# schematic.net
KiCad netlist of a schematic drawn in EAGLE
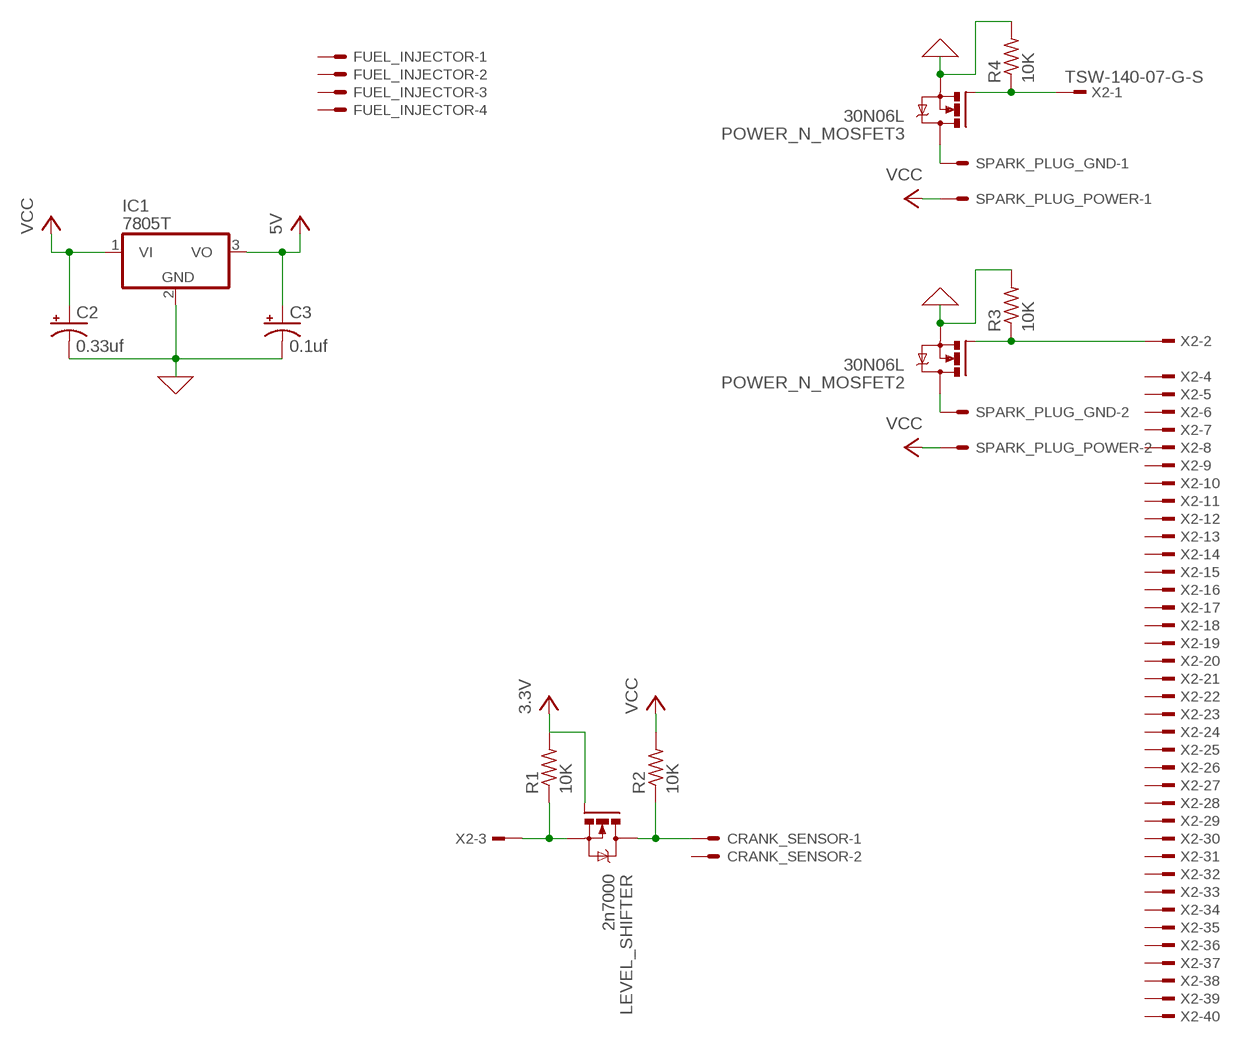
[diagram p0: schematic, sheet 1]

(export (version "E")
  (design (tool "Eeschema 10.0.6"))
  (components
    (comp (ref "C2")
      (value "0.33uf")
      (footprint "eagle-import:E2,5-5")
      (libsource (lib "eagle-import") (part "CPOL-USE2.5-5"))
    )
    (comp (ref "C3")
      (value "0.1uf")
      (footprint "eagle-import:E2,5-5")
      (libsource (lib "eagle-import") (part "CPOL-USE2.5-5"))
    )
    (comp (ref "CRANK_SENSOR")
      (value "KK-156-2")
      (footprint "eagle-import:KK-156-2")
      (fields (field (name "MF") "MOLEX"))
      (libsource (lib "eagle-import") (part "KK-156-2"))
    )
    (comp (ref "FUEL_INJECTOR")
      (value "KK-156-4")
      (footprint "eagle-import:KK-156-4")
      (fields (field (name "MF") "MOLEX"))
      (libsource (lib "eagle-import") (part "KK-156-4"))
    )
    (comp (ref "IC1")
      (value "7805T")
      (footprint "eagle-import:TO220H")
      (libsource (lib "eagle-import") (part "78T05"))
    )
    (comp (ref "LEVEL_SHIFTER")
      (value "2n7000")
      (footprint "eagle-import:TO220BV")
      (libsource (lib "eagle-import") (part "IRF520"))
    )
    (comp (ref "POWER_N_MOSFET2")
      (value "30N06L")
      (footprint "eagle-import:TO220BV")
      (libsource (lib "eagle-import") (part "IRF520"))
    )
    (comp (ref "POWER_N_MOSFET3")
      (value "30N06L")
      (footprint "eagle-import:TO220BV")
      (libsource (lib "eagle-import") (part "IRF520"))
    )
    (comp (ref "R1")
      (value "10K")
      (footprint "eagle-import:0207_7")
      (libsource (lib "eagle-import") (part "R-US_0207/7"))
    )
    (comp (ref "R2")
      (value "10K")
      (footprint "eagle-import:0207_7")
      (libsource (lib "eagle-import") (part "R-US_0207/7"))
    )
    (comp (ref "R3")
      (value "10K")
      (footprint "eagle-import:0207_7")
      (libsource (lib "eagle-import") (part "R-US_0207/7"))
    )
    (comp (ref "R4")
      (value "10K")
      (footprint "eagle-import:0207_7")
      (libsource (lib "eagle-import") (part "R-US_0207/7"))
    )
    (comp (ref "SPARK_PLUG_GND")
      (value "KK-156-2")
      (footprint "eagle-import:KK-156-2")
      (fields (field (name "MF") "MOLEX"))
      (libsource (lib "eagle-import") (part "KK-156-2"))
    )
    (comp (ref "SPARK_PLUG_POWER")
      (value "KK-156-2")
      (footprint "eagle-import:KK-156-2")
      (fields (field (name "MF") "MOLEX"))
      (libsource (lib "eagle-import") (part "KK-156-2"))
    )
    (comp (ref "X2")
      (value "TSW-140-07-G-S")
      (footprint "eagle-import:TSW-140-XX-G-S")
      (fields (field (name "MF") "Samtec Inc."))
      (libsource (lib "eagle-import") (part "TSW-140--G-S07"))
    )
  )
  (nets
    (net (code "1") (name "3.3V") (class "Default")
      (node (ref "LEVEL_SHIFTER") (pin "G") (pinfunction "G_G") (pintype "passive"))
      (node (ref "R1") (pin "2") (pinfunction "2_2") (pintype "passive"))
    )
    (net (code "2") (name "5V") (class "Default")
      (node (ref "C2") (pin "+") (pinfunction "+_+") (pintype "passive"))
      (node (ref "C3") (pin "+") (pinfunction "+_+") (pintype "passive"))
      (node (ref "IC1") (pin "1") (pinfunction "VI_1") (pintype "input"))
      (node (ref "IC1") (pin "3") (pinfunction "VO_3") (pintype "passive"))
      (node (ref "R2") (pin "2") (pinfunction "2_2") (pintype "passive"))
      (node (ref "SPARK_PLUG_POWER") (pin "1") (pinfunction "S_1") (pintype "passive"))
      (node (ref "SPARK_PLUG_POWER") (pin "2") (pinfunction "S_2") (pintype "passive"))
    )
    (net (code "3") (name "GND") (class "Default")
      (node (ref "C2") (pin "-") (pinfunction "-_-") (pintype "passive"))
      (node (ref "C3") (pin "-") (pinfunction "-_-") (pintype "passive"))
      (node (ref "IC1") (pin "2") (pinfunction "GND_2") (pintype "passive"))
      (node (ref "POWER_N_MOSFET2") (pin "S") (pinfunction "S_S") (pintype "passive"))
      (node (ref "POWER_N_MOSFET3") (pin "S") (pinfunction "S_S") (pintype "passive"))
      (node (ref "R3") (pin "2") (pinfunction "2_2") (pintype "passive"))
      (node (ref "R4") (pin "2") (pinfunction "2_2") (pintype "passive"))
    )
    (net (code "4") (name "Net-(CRANK_SENSORA-S)") (class "Default")
      (node (ref "CRANK_SENSOR") (pin "1") (pinfunction "S_1") (pintype "passive"))
      (node (ref "LEVEL_SHIFTER") (pin "D") (pinfunction "D_D") (pintype "passive"))
      (node (ref "R2") (pin "1") (pinfunction "1_1") (pintype "passive"))
    )
    (net (code "5") (name "Net-(POWER_N_MOSFET3-PadG)") (class "Default")
      (node (ref "POWER_N_MOSFET3") (pin "G") (pinfunction "G_G") (pintype "passive"))
      (node (ref "R4") (pin "1") (pinfunction "1_1") (pintype "passive"))
      (node (ref "X2") (pin "1") (pinfunction "1_1") (pintype "passive"))
    )
    (net (code "6") (name "Net-(SPARK_PLUG_GNDA-S)") (class "Default")
      (node (ref "POWER_N_MOSFET3") (pin "D") (pinfunction "D_D") (pintype "passive"))
      (node (ref "SPARK_PLUG_GND") (pin "1") (pinfunction "S_1") (pintype "passive"))
    )
    (net (code "7") (name "Net-(SPARK_PLUG_GNDB-S)") (class "Default")
      (node (ref "POWER_N_MOSFET2") (pin "D") (pinfunction "D_D") (pintype "passive"))
      (node (ref "SPARK_PLUG_GND") (pin "2") (pinfunction "S_2") (pintype "passive"))
    )
    (net (code "8") (name "Net-(X2L-1)") (class "Default")
      (node (ref "POWER_N_MOSFET2") (pin "G") (pinfunction "G_G") (pintype "passive"))
      (node (ref "R3") (pin "1") (pinfunction "1_1") (pintype "passive"))
      (node (ref "X2") (pin "2") (pinfunction "1_2") (pintype "passive"))
    )
    (net (code "9") (name "Net-(X2W-1)") (class "Default")
      (node (ref "LEVEL_SHIFTER") (pin "S") (pinfunction "S_S") (pintype "passive"))
      (node (ref "R1") (pin "1") (pinfunction "1_1") (pintype "passive"))
      (node (ref "X2") (pin "3") (pinfunction "1_3") (pintype "passive"))
    )
    (net (code "10") (name "unconnected-(CRANK_SENSORB-S-Pad2)") (class "Default")
      (node (ref "CRANK_SENSOR") (pin "2") (pinfunction "S_2") (pintype "passive"))
    )
    (net (code "11") (name "unconnected-(FUEL_INJECTORA-S-Pad1)") (class "Default")
      (node (ref "FUEL_INJECTOR") (pin "1") (pinfunction "S_1") (pintype "passive"))
    )
    (net (code "12") (name "unconnected-(FUEL_INJECTORB-S-Pad2)") (class "Default")
      (node (ref "FUEL_INJECTOR") (pin "2") (pinfunction "S_2") (pintype "passive"))
    )
    (net (code "13") (name "unconnected-(FUEL_INJECTORC-S-Pad3)") (class "Default")
      (node (ref "FUEL_INJECTOR") (pin "3") (pinfunction "S_3") (pintype "passive"))
    )
    (net (code "14") (name "unconnected-(FUEL_INJECTORD-S-Pad4)") (class "Default")
      (node (ref "FUEL_INJECTOR") (pin "4") (pinfunction "S_4") (pintype "passive"))
    )
    (net (code "15") (name "unconnected-(X2AA-1-Pad33)") (class "Default")
      (node (ref "X2") (pin "33") (pinfunction "1_33") (pintype "passive"))
    )
    (net (code "16") (name "unconnected-(X2AB-1-Pad34)") (class "Default")
      (node (ref "X2") (pin "34") (pinfunction "1_34") (pintype "passive"))
    )
    (net (code "17") (name "unconnected-(X2AC-1-Pad35)") (class "Default")
      (node (ref "X2") (pin "35") (pinfunction "1_35") (pintype "passive"))
    )
    (net (code "18") (name "unconnected-(X2AD-1-Pad36)") (class "Default")
      (node (ref "X2") (pin "36") (pinfunction "1_36") (pintype "passive"))
    )
    (net (code "19") (name "unconnected-(X2AE-1-Pad37)") (class "Default")
      (node (ref "X2") (pin "37") (pinfunction "1_37") (pintype "passive"))
    )
    (net (code "20") (name "unconnected-(X2AF-1-Pad38)") (class "Default")
      (node (ref "X2") (pin "38") (pinfunction "1_38") (pintype "passive"))
    )
    (net (code "21") (name "unconnected-(X2AG-1-Pad39)") (class "Default")
      (node (ref "X2") (pin "39") (pinfunction "1_39") (pintype "passive"))
    )
    (net (code "22") (name "unconnected-(X2AH-1-Pad4)") (class "Default")
      (node (ref "X2") (pin "4") (pinfunction "1_4") (pintype "passive"))
    )
    (net (code "23") (name "unconnected-(X2AI-1-Pad40)") (class "Default")
      (node (ref "X2") (pin "40") (pinfunction "1_40") (pintype "passive"))
    )
    (net (code "24") (name "unconnected-(X2AJ-1-Pad5)") (class "Default")
      (node (ref "X2") (pin "5") (pinfunction "1_5") (pintype "passive"))
    )
    (net (code "25") (name "unconnected-(X2AK-1-Pad6)") (class "Default")
      (node (ref "X2") (pin "6") (pinfunction "1_6") (pintype "passive"))
    )
    (net (code "26") (name "unconnected-(X2AL-1-Pad7)") (class "Default")
      (node (ref "X2") (pin "7") (pinfunction "1_7") (pintype "passive"))
    )
    (net (code "27") (name "unconnected-(X2AM-1-Pad8)") (class "Default")
      (node (ref "X2") (pin "8") (pinfunction "1_8") (pintype "passive"))
    )
    (net (code "28") (name "unconnected-(X2AN-1-Pad9)") (class "Default")
      (node (ref "X2") (pin "9") (pinfunction "1_9") (pintype "passive"))
    )
    (net (code "29") (name "unconnected-(X2B-1-Pad10)") (class "Default")
      (node (ref "X2") (pin "10") (pinfunction "1_10") (pintype "passive"))
    )
    (net (code "30") (name "unconnected-(X2C-1-Pad11)") (class "Default")
      (node (ref "X2") (pin "11") (pinfunction "1_11") (pintype "passive"))
    )
    (net (code "31") (name "unconnected-(X2D-1-Pad12)") (class "Default")
      (node (ref "X2") (pin "12") (pinfunction "1_12") (pintype "passive"))
    )
    (net (code "32") (name "unconnected-(X2E-1-Pad13)") (class "Default")
      (node (ref "X2") (pin "13") (pinfunction "1_13") (pintype "passive"))
    )
    (net (code "33") (name "unconnected-(X2F-1-Pad14)") (class "Default")
      (node (ref "X2") (pin "14") (pinfunction "1_14") (pintype "passive"))
    )
    (net (code "34") (name "unconnected-(X2G-1-Pad15)") (class "Default")
      (node (ref "X2") (pin "15") (pinfunction "1_15") (pintype "passive"))
    )
    (net (code "35") (name "unconnected-(X2H-1-Pad16)") (class "Default")
      (node (ref "X2") (pin "16") (pinfunction "1_16") (pintype "passive"))
    )
    (net (code "36") (name "unconnected-(X2I-1-Pad17)") (class "Default")
      (node (ref "X2") (pin "17") (pinfunction "1_17") (pintype "passive"))
    )
    (net (code "37") (name "unconnected-(X2J-1-Pad18)") (class "Default")
      (node (ref "X2") (pin "18") (pinfunction "1_18") (pintype "passive"))
    )
    (net (code "38") (name "unconnected-(X2K-1-Pad19)") (class "Default")
      (node (ref "X2") (pin "19") (pinfunction "1_19") (pintype "passive"))
    )
    (net (code "39") (name "unconnected-(X2M-1-Pad20)") (class "Default")
      (node (ref "X2") (pin "20") (pinfunction "1_20") (pintype "passive"))
    )
    (net (code "40") (name "unconnected-(X2N-1-Pad21)") (class "Default")
      (node (ref "X2") (pin "21") (pinfunction "1_21") (pintype "passive"))
    )
    (net (code "41") (name "unconnected-(X2O-1-Pad22)") (class "Default")
      (node (ref "X2") (pin "22") (pinfunction "1_22") (pintype "passive"))
    )
    (net (code "42") (name "unconnected-(X2P-1-Pad23)") (class "Default")
      (node (ref "X2") (pin "23") (pinfunction "1_23") (pintype "passive"))
    )
    (net (code "43") (name "unconnected-(X2Q-1-Pad24)") (class "Default")
      (node (ref "X2") (pin "24") (pinfunction "1_24") (pintype "passive"))
    )
    (net (code "44") (name "unconnected-(X2R-1-Pad25)") (class "Default")
      (node (ref "X2") (pin "25") (pinfunction "1_25") (pintype "passive"))
    )
    (net (code "45") (name "unconnected-(X2S-1-Pad26)") (class "Default")
      (node (ref "X2") (pin "26") (pinfunction "1_26") (pintype "passive"))
    )
    (net (code "46") (name "unconnected-(X2T-1-Pad27)") (class "Default")
      (node (ref "X2") (pin "27") (pinfunction "1_27") (pintype "passive"))
    )
    (net (code "47") (name "unconnected-(X2U-1-Pad28)") (class "Default")
      (node (ref "X2") (pin "28") (pinfunction "1_28") (pintype "passive"))
    )
    (net (code "48") (name "unconnected-(X2V-1-Pad29)") (class "Default")
      (node (ref "X2") (pin "29") (pinfunction "1_29") (pintype "passive"))
    )
    (net (code "49") (name "unconnected-(X2X-1-Pad30)") (class "Default")
      (node (ref "X2") (pin "30") (pinfunction "1_30") (pintype "passive"))
    )
    (net (code "50") (name "unconnected-(X2Y-1-Pad31)") (class "Default")
      (node (ref "X2") (pin "31") (pinfunction "1_31") (pintype "passive"))
    )
    (net (code "51") (name "unconnected-(X2Z-1-Pad32)") (class "Default")
      (node (ref "X2") (pin "32") (pinfunction "1_32") (pintype "passive"))
    )
  )
)
